# MCU.net
KiCad netlist of a schematic drawn in Altium Designer
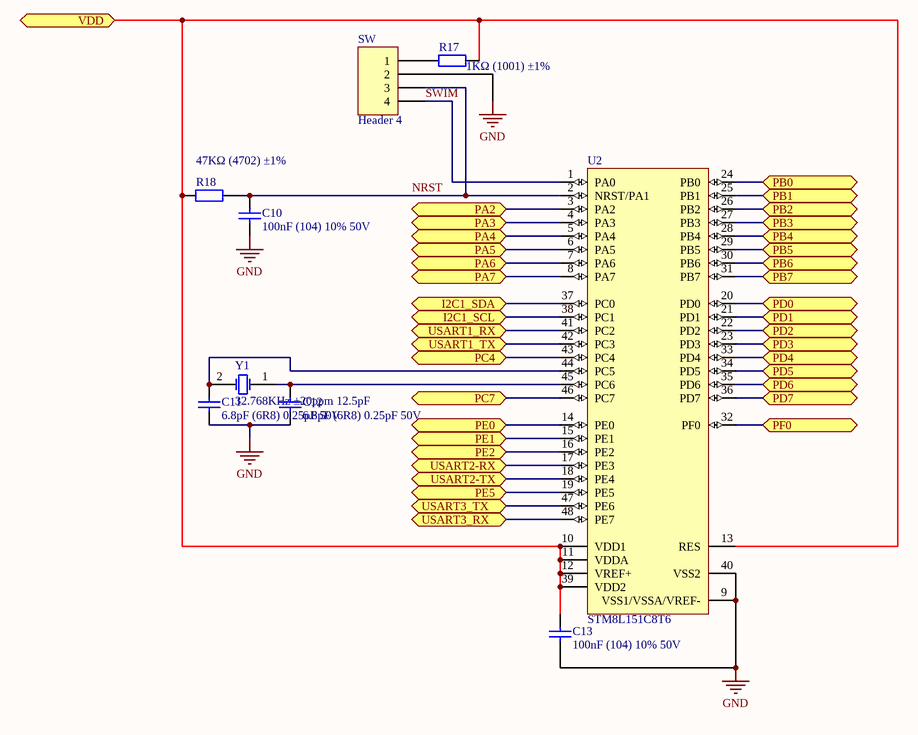
[diagram p0: MCU.SchDoc]

(export (version "E")
  (design (tool "Eeschema 10.0.6"))
  (components
    (comp (ref "C10")
      (value "100nF (104) 10% 50V")
      (footprint "0603_C")
      (description "贴片电容")
      (libsource (lib "Miscellaneous Devices LC") (part "0603 100nF (104) 10% 50V"))
    )
    (comp (ref "C11")
      (value "6.8pF (6R8) 0.25pF 50V")
      (footprint "0603_C")
      (description "贴片电容")
      (libsource (lib "Miscellaneous Devices LC") (part "0603 6.8pF (6R8) 0.25pF 50V"))
    )
    (comp (ref "C12")
      (value "6.8pF (6R8) 0.25pF 50V")
      (footprint "0603_C")
      (description "贴片电容")
      (libsource (lib "Miscellaneous Devices LC") (part "0603 6.8pF (6R8) 0.25pF 50V"))
    )
    (comp (ref "C13")
      (value "100nF (104) 10% 50V")
      (footprint "0603_C")
      (description "贴片电容")
      (libsource (lib "Miscellaneous Devices LC") (part "0603 100nF (104) 10% 50V"))
    )
    (comp (ref "R17")
      (value "1KΩ (1001) ±1%")
      (footprint "0603_R")
      (description "贴片电阻")
      (libsource (lib "Miscellaneous Devices LC") (part "0603 1KΩ (1001) 1%"))
    )
    (comp (ref "R18")
      (value "47KΩ (4702) ±1%")
      (footprint "0603_R")
      (description "贴片电阻")
      (libsource (lib "Miscellaneous Devices LC") (part "0603 100KΩ (1003) 1%"))
    )
    (comp (ref "SW")
      (value "Header 4")
      (footprint "HDR1X4")
      (description "Header, 4-Pin")
      (fields (field (name "PUBLISHER") "Altium Limited"))
      (libsource (lib "Miscellaneous Connectors") (part "Header 4"))
    )
    (comp (ref "U2")
      (value "STM8L151C8T6")
      (footprint "LQFP48_M")
      (libsource (lib "STMicroelectronics STM8L") (part "STM8L151C8T6"))
    )
    (comp (ref "Y1")
      (value "32.768KHz ±20ppm 12.5pF")
      (footprint "SMD-3215_2P FC - 135")
      (description "贴片晶振")
      (libsource (lib "Miscellaneous Devices LC") (part "SMD-3215_2P 32.768KHz 20ppm 12.5pF"))
    )
  )
  (nets
    (net (code "1") (name "/I2C1_SCL") (class "Default")
      (node (ref "U2") (pin "38") (pinfunction "PC1_38") (pintype "bidirectional"))
    )
    (net (code "2") (name "/I2C1_SDA") (class "Default")
      (node (ref "U2") (pin "37") (pinfunction "PC0_37") (pintype "bidirectional"))
    )
    (net (code "3") (name "/NRST") (class "Default")
      (node (ref "C10") (pin "2") (pinfunction "2_2") (pintype "passive"))
      (node (ref "R18") (pin "1") (pinfunction "1_1") (pintype "passive"))
      (node (ref "SW") (pin "3") (pinfunction "3_3") (pintype "passive"))
      (node (ref "U2") (pin "2") (pinfunction "NRST/PA1_2") (pintype "bidirectional"))
    )
    (net (code "4") (name "/PA2") (class "Default")
      (node (ref "U2") (pin "3") (pinfunction "PA2_3") (pintype "bidirectional"))
    )
    (net (code "5") (name "/PA3") (class "Default")
      (node (ref "U2") (pin "4") (pinfunction "PA3_4") (pintype "bidirectional"))
    )
    (net (code "6") (name "/PA4") (class "Default")
      (node (ref "U2") (pin "5") (pinfunction "PA4_5") (pintype "bidirectional"))
    )
    (net (code "7") (name "/PA5") (class "Default")
      (node (ref "U2") (pin "6") (pinfunction "PA5_6") (pintype "bidirectional"))
    )
    (net (code "8") (name "/PA6") (class "Default")
      (node (ref "U2") (pin "7") (pinfunction "PA6_7") (pintype "bidirectional"))
    )
    (net (code "9") (name "/PA7") (class "Default")
      (node (ref "U2") (pin "8") (pinfunction "PA7_8") (pintype "bidirectional"))
    )
    (net (code "10") (name "/PB0") (class "Default")
      (node (ref "U2") (pin "24") (pinfunction "PB0_24") (pintype "bidirectional"))
    )
    (net (code "11") (name "/PB1") (class "Default")
      (node (ref "U2") (pin "25") (pinfunction "PB1_25") (pintype "bidirectional"))
    )
    (net (code "12") (name "/PB2") (class "Default")
      (node (ref "U2") (pin "26") (pinfunction "PB2_26") (pintype "bidirectional"))
    )
    (net (code "13") (name "/PB3") (class "Default")
      (node (ref "U2") (pin "27") (pinfunction "PB3_27") (pintype "bidirectional"))
    )
    (net (code "14") (name "/PB4") (class "Default")
      (node (ref "U2") (pin "28") (pinfunction "PB4_28") (pintype "bidirectional"))
    )
    (net (code "15") (name "/PB5") (class "Default")
      (node (ref "U2") (pin "29") (pinfunction "PB5_29") (pintype "bidirectional"))
    )
    (net (code "16") (name "/PB6") (class "Default")
      (node (ref "U2") (pin "30") (pinfunction "PB6_30") (pintype "bidirectional"))
    )
    (net (code "17") (name "/PB7") (class "Default")
      (node (ref "U2") (pin "31") (pinfunction "PB7_31") (pintype "bidirectional"))
    )
    (net (code "18") (name "/PC4") (class "Default")
      (node (ref "U2") (pin "43") (pinfunction "PC4_43") (pintype "bidirectional"))
    )
    (net (code "19") (name "/PC7") (class "Default")
      (node (ref "U2") (pin "46") (pinfunction "PC7_46") (pintype "bidirectional"))
    )
    (net (code "20") (name "/PD0") (class "Default")
      (node (ref "U2") (pin "20") (pinfunction "PD0_20") (pintype "bidirectional"))
    )
    (net (code "21") (name "/PD1") (class "Default")
      (node (ref "U2") (pin "21") (pinfunction "PD1_21") (pintype "bidirectional"))
    )
    (net (code "22") (name "/PD2") (class "Default")
      (node (ref "U2") (pin "22") (pinfunction "PD2_22") (pintype "bidirectional"))
    )
    (net (code "23") (name "/PD3") (class "Default")
      (node (ref "U2") (pin "23") (pinfunction "PD3_23") (pintype "bidirectional"))
    )
    (net (code "24") (name "/PD4") (class "Default")
      (node (ref "U2") (pin "33") (pinfunction "PD4_33") (pintype "bidirectional"))
    )
    (net (code "25") (name "/PD5") (class "Default")
      (node (ref "U2") (pin "34") (pinfunction "PD5_34") (pintype "bidirectional"))
    )
    (net (code "26") (name "/PD6") (class "Default")
      (node (ref "U2") (pin "35") (pinfunction "PD6_35") (pintype "bidirectional"))
    )
    (net (code "27") (name "/PD7") (class "Default")
      (node (ref "U2") (pin "36") (pinfunction "PD7_36") (pintype "bidirectional"))
    )
    (net (code "28") (name "/PE0") (class "Default")
      (node (ref "U2") (pin "14") (pinfunction "PE0_14") (pintype "bidirectional"))
    )
    (net (code "29") (name "/PE1") (class "Default")
      (node (ref "U2") (pin "15") (pinfunction "PE1_15") (pintype "bidirectional"))
    )
    (net (code "30") (name "/PE2") (class "Default")
      (node (ref "U2") (pin "16") (pinfunction "PE2_16") (pintype "bidirectional"))
    )
    (net (code "31") (name "/PE5") (class "Default")
      (node (ref "U2") (pin "19") (pinfunction "PE5_19") (pintype "bidirectional"))
    )
    (net (code "32") (name "/PF0") (class "Default")
      (node (ref "U2") (pin "32") (pinfunction "PF0_32") (pintype "bidirectional"))
    )
    (net (code "33") (name "/SWIM") (class "Default")
      (node (ref "SW") (pin "4") (pinfunction "4_4") (pintype "passive"))
      (node (ref "U2") (pin "1") (pinfunction "PA0_1") (pintype "bidirectional"))
    )
    (net (code "34") (name "/USART1_RX") (class "Default")
      (node (ref "U2") (pin "41") (pinfunction "PC2_41") (pintype "bidirectional"))
    )
    (net (code "35") (name "/USART1_TX") (class "Default")
      (node (ref "U2") (pin "42") (pinfunction "PC3_42") (pintype "bidirectional"))
    )
    (net (code "36") (name "/USART2-RX") (class "Default")
      (node (ref "U2") (pin "17") (pinfunction "PE3_17") (pintype "bidirectional"))
    )
    (net (code "37") (name "/USART2-TX") (class "Default")
      (node (ref "U2") (pin "18") (pinfunction "PE4_18") (pintype "bidirectional"))
    )
    (net (code "38") (name "/USART3_RX") (class "Default")
      (node (ref "U2") (pin "48") (pinfunction "PE7_48") (pintype "bidirectional"))
    )
    (net (code "39") (name "/USART3_TX") (class "Default")
      (node (ref "U2") (pin "47") (pinfunction "PE6_47") (pintype "bidirectional"))
    )
    (net (code "40") (name "/VDD") (class "Default")
      (node (ref "C13") (pin "2") (pinfunction "2_2") (pintype "passive"))
      (node (ref "R17") (pin "2") (pinfunction "2_2") (pintype "passive"))
      (node (ref "R18") (pin "2") (pinfunction "2_2") (pintype "passive"))
      (node (ref "U2") (pin "10") (pinfunction "VDD1_10") (pintype "power_in"))
      (node (ref "U2") (pin "11") (pinfunction "VDDA_11") (pintype "power_in"))
      (node (ref "U2") (pin "12") (pinfunction "VREF+_12") (pintype "power_in"))
      (node (ref "U2") (pin "13") (pinfunction "RES_13") (pintype "passive"))
      (node (ref "U2") (pin "39") (pinfunction "VDD2_39") (pintype "power_in"))
    )
    (net (code "41") (name "GND") (class "Default")
      (node (ref "C10") (pin "1") (pinfunction "1_1") (pintype "passive"))
      (node (ref "C11") (pin "1") (pinfunction "1_1") (pintype "passive"))
      (node (ref "C12") (pin "1") (pinfunction "1_1") (pintype "passive"))
      (node (ref "C13") (pin "1") (pinfunction "1_1") (pintype "passive"))
      (node (ref "SW") (pin "2") (pinfunction "2_2") (pintype "passive"))
      (node (ref "U2") (pin "40") (pinfunction "VSS2_40") (pintype "power_in"))
      (node (ref "U2") (pin "9") (pinfunction "VSS1/VSSA/VREF-_9") (pintype "power_in"))
    )
    (net (code "42") (name "Net-(R17-Pad1)") (class "Default")
      (node (ref "R17") (pin "1") (pinfunction "1_1") (pintype "passive"))
      (node (ref "SW") (pin "1") (pinfunction "1_1") (pintype "passive"))
    )
    (net (code "43") (name "Net-(U2-PC5)") (class "Default")
      (node (ref "C11") (pin "2") (pinfunction "2_2") (pintype "passive"))
      (node (ref "U2") (pin "44") (pinfunction "PC5_44") (pintype "bidirectional"))
      (node (ref "Y1") (pin "2") (pinfunction "OSC2_2") (pintype "passive"))
    )
    (net (code "44") (name "Net-(U2-PC6)") (class "Default")
      (node (ref "C12") (pin "2") (pinfunction "2_2") (pintype "passive"))
      (node (ref "U2") (pin "45") (pinfunction "PC6_45") (pintype "bidirectional"))
      (node (ref "Y1") (pin "1") (pinfunction "OSC1_1") (pintype "passive"))
    )
  )
)
